# USB_Connector.net
KiCad netlist of a schematic drawn in Altium Designer
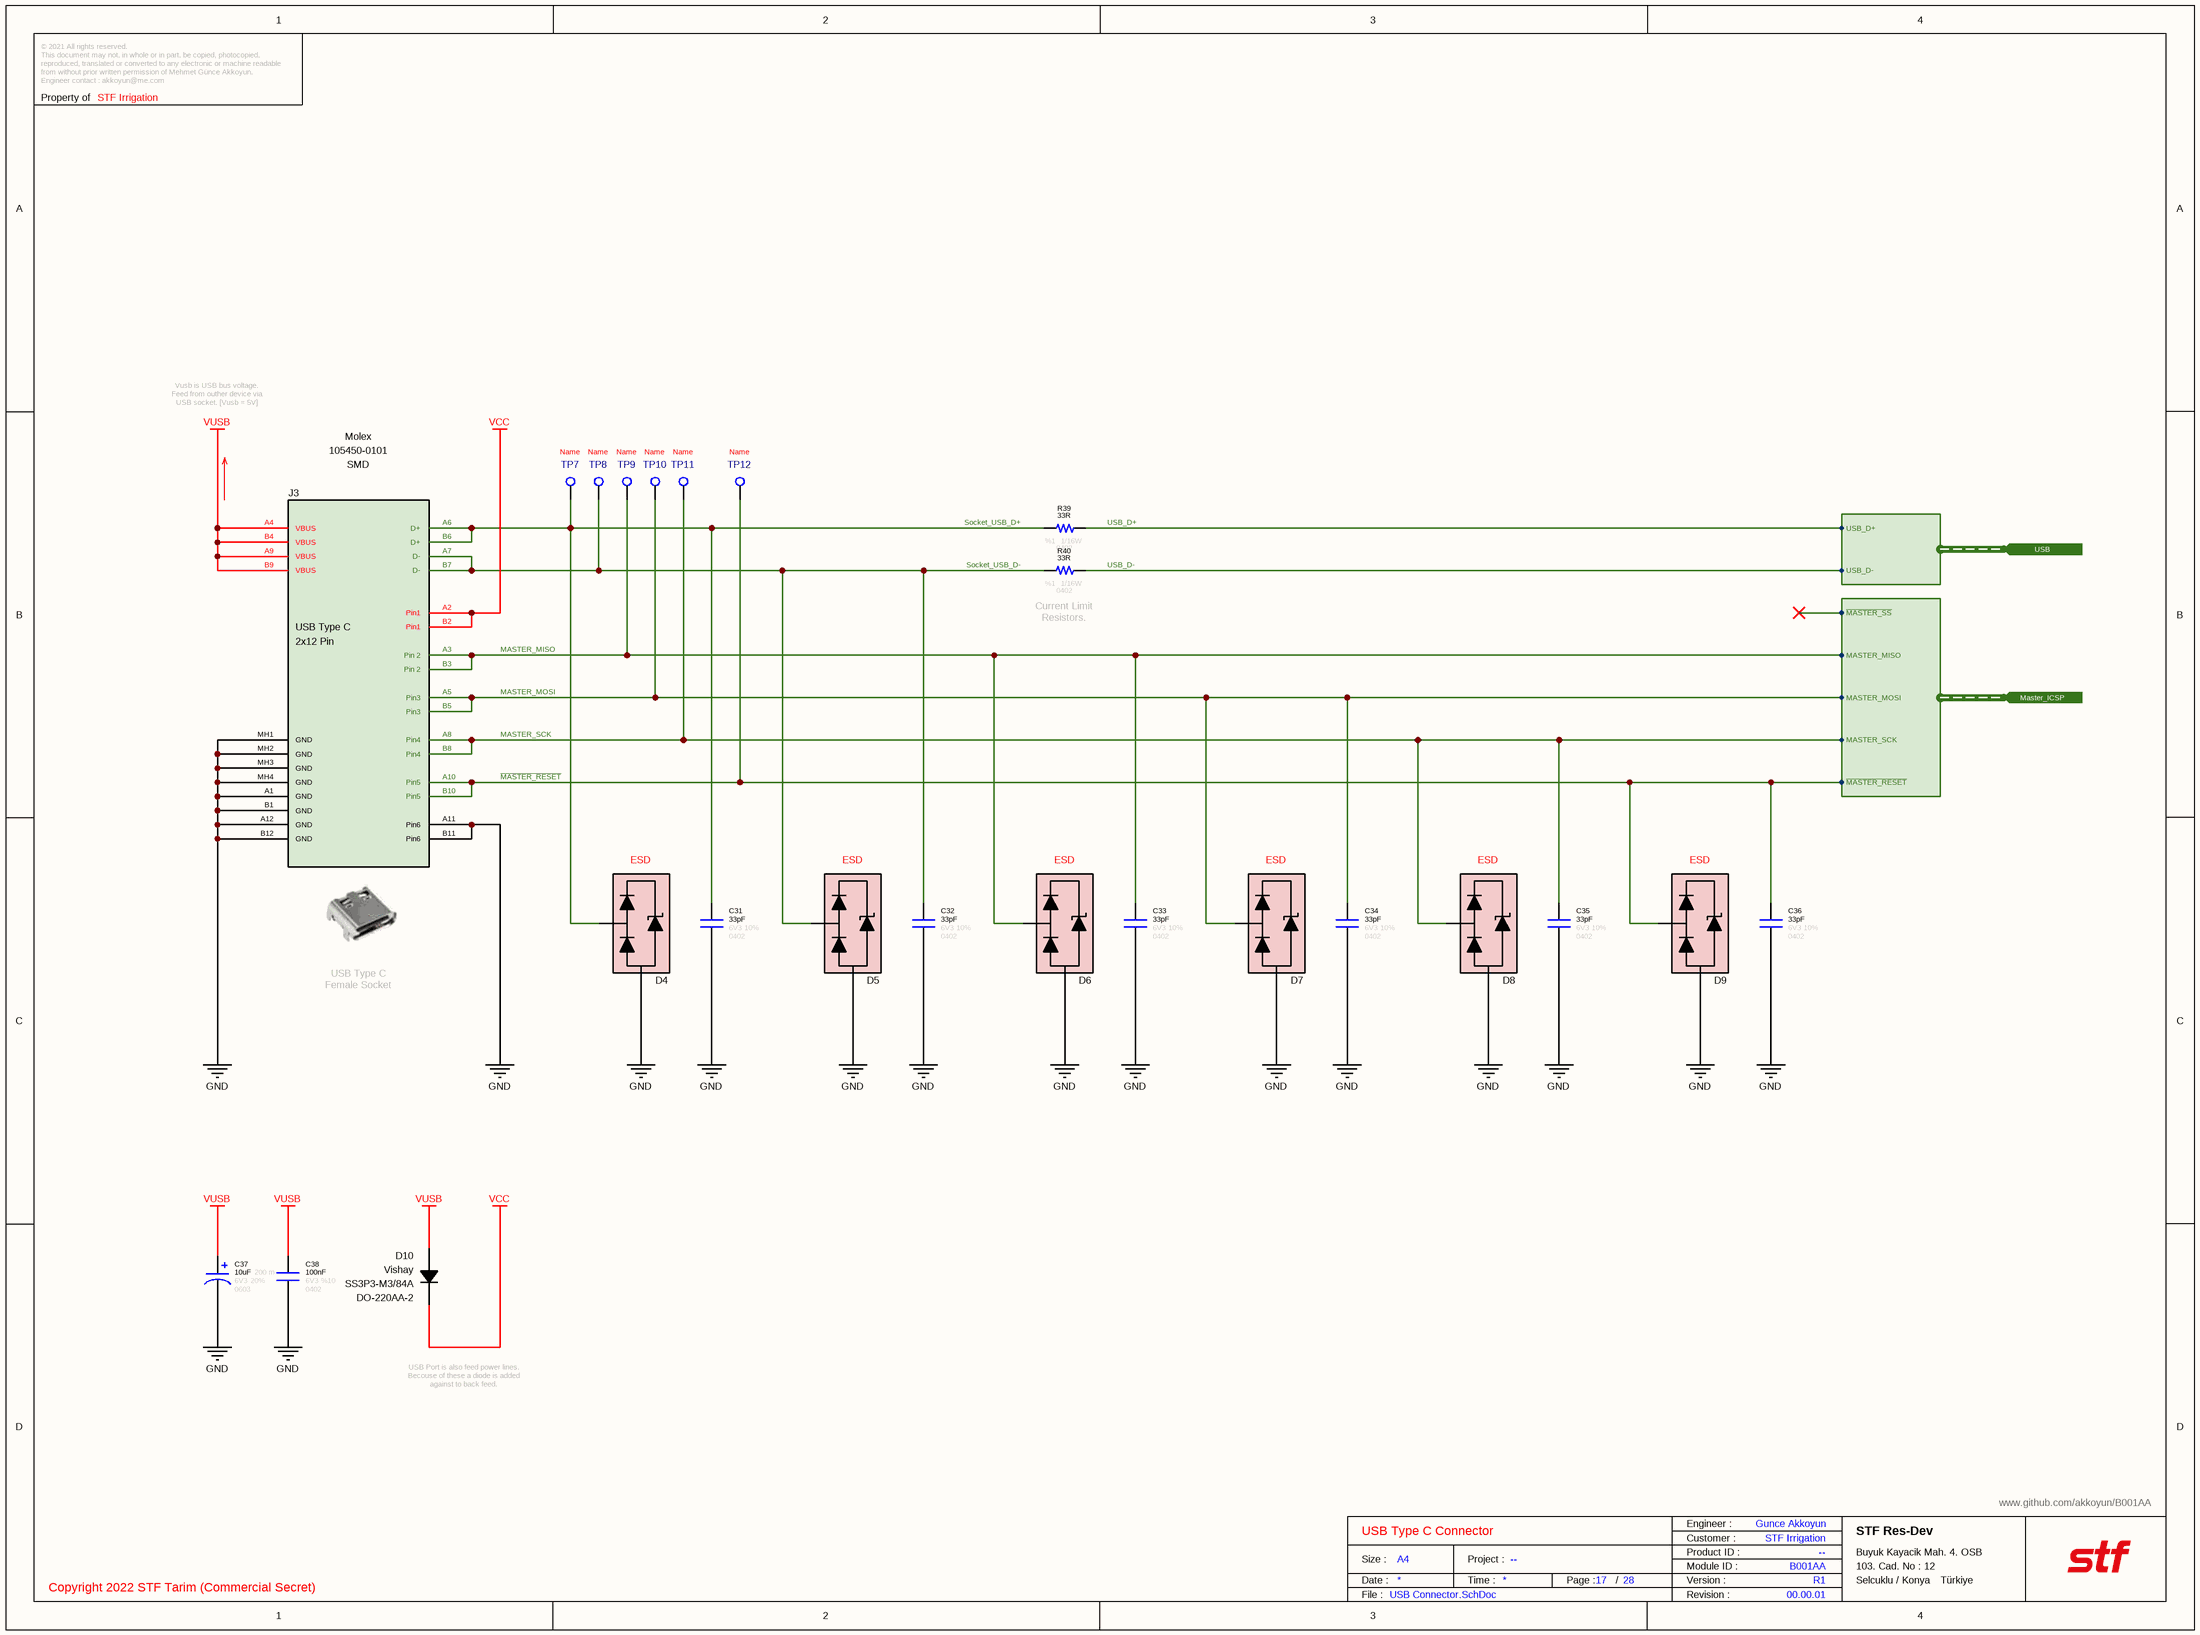
[diagram p0: USB Connector.SchDoc]

(export (version "E")
  (design (tool "Eeschema 10.0.6"))
  (components
    (comp (ref "C31")
      (value "33pF")
      (footprint "CAPACITOR_0402")
      (description "Capacitor - 33pF [0402] (Ceramic)")
      (fields
        (field (name "MANUFACTURER PART NUMBER") "C0402C330J9RACAUTO")
        (field (name "TOLERANCE") "10%")
        (field (name "CASE") "0402")
        (field (name "VOLTAGE") "6V3")
      )
      (libsource (lib "P101DA_Library") (part "Capacitor - 33pF [0402-6V3]"))
    )
    (comp (ref "C32")
      (value "33pF")
      (footprint "CAPACITOR_0402")
      (description "Capacitor - 33pF [0402] (Ceramic)")
      (fields
        (field (name "MANUFACTURER PART NUMBER") "C0402C330J9RACAUTO")
        (field (name "TOLERANCE") "10%")
        (field (name "CASE") "0402")
        (field (name "VOLTAGE") "6V3")
      )
      (libsource (lib "P101DA_Library") (part "Capacitor - 33pF [0402-6V3]"))
    )
    (comp (ref "C33")
      (value "33pF")
      (footprint "CAPACITOR_0402")
      (description "Capacitor - 33pF [0402] (Ceramic)")
      (fields
        (field (name "MANUFACTURER PART NUMBER") "C0402C330J9RACAUTO")
        (field (name "TOLERANCE") "10%")
        (field (name "CASE") "0402")
        (field (name "VOLTAGE") "6V3")
      )
      (libsource (lib "P101DA_Library") (part "Capacitor - 33pF [0402-6V3]"))
    )
    (comp (ref "C34")
      (value "33pF")
      (footprint "CAPACITOR_0402")
      (description "Capacitor - 33pF [0402] (Ceramic)")
      (fields
        (field (name "MANUFACTURER PART NUMBER") "C0402C330J9RACAUTO")
        (field (name "TOLERANCE") "10%")
        (field (name "CASE") "0402")
        (field (name "VOLTAGE") "6V3")
      )
      (libsource (lib "P101DA_Library") (part "Capacitor - 33pF [0402-6V3]"))
    )
    (comp (ref "C35")
      (value "33pF")
      (footprint "CAPACITOR_0402")
      (description "Capacitor - 33pF [0402] (Ceramic)")
      (fields
        (field (name "MANUFACTURER PART NUMBER") "C0402C330J9RACAUTO")
        (field (name "TOLERANCE") "10%")
        (field (name "CASE") "0402")
        (field (name "VOLTAGE") "6V3")
      )
      (libsource (lib "P101DA_Library") (part "Capacitor - 33pF [0402-6V3]"))
    )
    (comp (ref "C36")
      (value "33pF")
      (footprint "CAPACITOR_0402")
      (description "Capacitor - 33pF [0402] (Ceramic)")
      (fields
        (field (name "MANUFACTURER PART NUMBER") "C0402C330J9RACAUTO")
        (field (name "TOLERANCE") "10%")
        (field (name "CASE") "0402")
        (field (name "VOLTAGE") "6V3")
      )
      (libsource (lib "P101DA_Library") (part "Capacitor - 33pF [0402-6V3]"))
    )
    (comp (ref "C37")
      (value "10uF")
      (footprint "CAPACITOR_0603_Tantalum")
      (description "Capacitor - 10uF [0603] (Tantalium)")
      (fields
        (field (name "MANUFACTURER PART NUMBER") "F380J106MMAAH3")
        (field (name "ESR") "200 m")
        (field (name "TOLERANCE") "20%")
        (field (name "CASE") "0603")
        (field (name "VOLTAGE") "6V3")
        (field (name "Comment") "Capacitor - 10uF [0603] (Tantalum)")
      )
      (libsource (lib "P101DA_Library") (part "Capacitor - 10uF [0603-6V3] (Tantalium)"))
    )
    (comp (ref "C38")
      (value "100nF")
      (footprint "CAPACITOR_0402")
      (description "Capacitor - 100nF [0402-6V3] (Ceramic)")
      (fields
        (field (name "MANUFACTURER PART NUMBER") "04026D104KAT4A")
        (field (name "TOLERANCE") "%10")
        (field (name "VOLTAGE") "6V3")
        (field (name "CASE") "0402")
        (field (name "Comment") "Capacitor - 100nF [0402] (Ceramic)")
      )
      (libsource (lib "P101DA_Library") (part "Capacitor - 100nF [0402-6V3]"))
    )
    (comp (ref "D4")
      (value "0402ESDA-MLP1")
      (footprint "ESD_0402")
      (description "SUPPRESSOR ESD 30VDC 0402 HFREE")
      (libsource (lib "P101DA_Library") (part "Diode - TPD1E05U06DPYR"))
    )
    (comp (ref "D5")
      (value "0402ESDA-MLP1")
      (footprint "ESD_0402")
      (description "SUPPRESSOR ESD 30VDC 0402 HFREE")
      (libsource (lib "P101DA_Library") (part "Diode - TPD1E05U06DPYR"))
    )
    (comp (ref "D6")
      (value "0402ESDA-MLP1")
      (footprint "ESD_0402")
      (description "SUPPRESSOR ESD 30VDC 0402 HFREE")
      (libsource (lib "P101DA_Library") (part "Diode - TPD1E05U06DPYR"))
    )
    (comp (ref "D7")
      (value "0402ESDA-MLP1")
      (footprint "ESD_0402")
      (description "SUPPRESSOR ESD 30VDC 0402 HFREE")
      (libsource (lib "P101DA_Library") (part "Diode - TPD1E05U06DPYR"))
    )
    (comp (ref "D8")
      (value "0402ESDA-MLP1")
      (footprint "ESD_0402")
      (description "SUPPRESSOR ESD 30VDC 0402 HFREE")
      (libsource (lib "P101DA_Library") (part "Diode - TPD1E05U06DPYR"))
    )
    (comp (ref "D9")
      (value "0402ESDA-MLP1")
      (footprint "ESD_0402")
      (description "SUPPRESSOR ESD 30VDC 0402 HFREE")
      (libsource (lib "P101DA_Library") (part "Diode - TPD1E05U06DPYR"))
    )
    (comp (ref "D10")
      (value "SS3P3-M3/84A")
      (footprint "DO-220AA-2")
      (description "Schottky Diodes & Rectifiers 3.0 Amp 30 Volt 50 Amp IFSM")
      (fields
        (field (name "MANUFACTURER NAME") "Vishay")
        (field (name "MANUFACTURER PART NUMBER") "SS3P3-M3/84A")
        (field (name "CASE") "DO-220AA-2")
      )
      (libsource (lib "P101DA_Library") (part "Diode - SS3P3M384A"))
    )
    (comp (ref "J3")
      (value "105450-0101")
      (footprint "USB Type C - Molex 105450-0101")
      (description "USB Shielded I/O Receptacle; Type C; Right Angle; Surface Mount; Gold over Nickel")
      (fields
        (field (name "MANUFACTURER NAME") "Molex")
        (field (name "MANUFACTURER PART NUMBER") "105450-0101")
        (field (name "CASE") "SMD")
      )
      (libsource (lib "P101DA_Library") (part "Connector - USB Type C SMD Connector"))
    )
    (comp (ref "R39")
      (value "33R")
      (footprint "RESISTOR_0402")
      (description "Thick Film Resistors - SMD 1/16 W 33 Ohm 1%")
      (fields
        (field (name "MANUFACTURER PART NUMBER") "CRCW040233R0FKED")
        (field (name "CASE") "0402")
        (field (name "TOLERANCE") "%1")
        (field (name "POWER") "1/16W")
        (field (name "Comment") "33R - 0402 - %1 - 1/16W")
      )
      (libsource (lib "P101DA_Library") (part "Resistor - 33R [0402]"))
    )
    (comp (ref "R40")
      (value "33R")
      (footprint "RESISTOR_0402")
      (description "Thick Film Resistors - SMD 1/16 W 33 Ohm 1%")
      (fields
        (field (name "MANUFACTURER PART NUMBER") "CRCW040233R0FKED")
        (field (name "CASE") "0402")
        (field (name "TOLERANCE") "%1")
        (field (name "POWER") "1/16W")
        (field (name "Comment") "33R - 0402 - %1 - 1/16W")
      )
      (libsource (lib "P101DA_Library") (part "Resistor - 33R [0402]"))
    )
    (comp (ref "TP7")
      (value "PCB - Test Point")
      (footprint "Test_Point")
      (description "Test Point")
      (fields (field (name "NAME") "Name"))
      (libsource (lib "P101DA_Library") (part "PCB - Test Point"))
    )
    (comp (ref "TP8")
      (value "PCB - Test Point")
      (footprint "Test_Point")
      (description "Test Point")
      (fields (field (name "NAME") "Name"))
      (libsource (lib "P101DA_Library") (part "PCB - Test Point"))
    )
    (comp (ref "TP9")
      (value "PCB - Test Point")
      (footprint "Test_Point")
      (description "Test Point")
      (fields (field (name "NAME") "Name"))
      (libsource (lib "P101DA_Library") (part "PCB - Test Point"))
    )
    (comp (ref "TP10")
      (value "PCB - Test Point")
      (footprint "Test_Point")
      (description "Test Point")
      (fields (field (name "NAME") "Name"))
      (libsource (lib "P101DA_Library") (part "PCB - Test Point"))
    )
    (comp (ref "TP11")
      (value "PCB - Test Point")
      (footprint "Test_Point")
      (description "Test Point")
      (fields (field (name "NAME") "Name"))
      (libsource (lib "P101DA_Library") (part "PCB - Test Point"))
    )
    (comp (ref "TP12")
      (value "PCB - Test Point")
      (footprint "Test_Point")
      (description "Test Point")
      (fields (field (name "NAME") "Name"))
      (libsource (lib "P101DA_Library") (part "PCB - Test Point"))
    )
  )
  (nets
    (net (code "3") (name "/MASTER_MISO") (class "Default")
      (node (ref "C33") (pin "2") (pinfunction "2_2") (pintype "passive"))
      (node (ref "D6") (pin "1") (pinfunction "I/O_1") (pintype "passive"))
      (node (ref "J3") (pin "A3") (pinfunction "Pin_2_A3") (pintype "passive"))
      (node (ref "J3") (pin "B3") (pinfunction "Pin_2_B3") (pintype "passive"))
      (node (ref "TP9") (pin "1") (pinfunction "1_1") (pintype "passive"))
    )
    (net (code "4") (name "/MASTER_MOSI") (class "Default")
      (node (ref "C34") (pin "2") (pinfunction "2_2") (pintype "passive"))
      (node (ref "D7") (pin "1") (pinfunction "I/O_1") (pintype "passive"))
      (node (ref "J3") (pin "A5") (pinfunction "Pin3_A5") (pintype "passive"))
      (node (ref "J3") (pin "B5") (pinfunction "Pin3_B5") (pintype "passive"))
      (node (ref "TP10") (pin "1") (pinfunction "1_1") (pintype "passive"))
    )
    (net (code "5") (name "/MASTER_SCK") (class "Default")
      (node (ref "C35") (pin "2") (pinfunction "2_2") (pintype "passive"))
      (node (ref "D8") (pin "1") (pinfunction "I/O_1") (pintype "passive"))
      (node (ref "J3") (pin "A8") (pinfunction "Pin4_A8") (pintype "passive"))
      (node (ref "J3") (pin "B8") (pinfunction "Pin4_B8") (pintype "passive"))
      (node (ref "TP11") (pin "1") (pinfunction "1_1") (pintype "passive"))
    )
    (net (code "6") (name "/Socket_USB_D+") (class "Default")
      (node (ref "C31") (pin "2") (pinfunction "2_2") (pintype "passive"))
      (node (ref "D4") (pin "1") (pinfunction "I/O_1") (pintype "passive"))
      (node (ref "J3") (pin "A6") (pinfunction "D+_A6") (pintype "passive"))
      (node (ref "J3") (pin "B6") (pinfunction "D+_B6") (pintype "passive"))
      (node (ref "R39") (pin "2") (pinfunction "2_2") (pintype "passive"))
      (node (ref "TP7") (pin "1") (pinfunction "1_1") (pintype "passive"))
    )
    (net (code "7") (name "/Socket_USB_D-") (class "Default")
      (node (ref "C32") (pin "2") (pinfunction "2_2") (pintype "passive"))
      (node (ref "D5") (pin "1") (pinfunction "I/O_1") (pintype "passive"))
      (node (ref "J3") (pin "A7") (pinfunction "D-_A7") (pintype "passive"))
      (node (ref "J3") (pin "B7") (pinfunction "D-_B7") (pintype "passive"))
      (node (ref "R40") (pin "2") (pinfunction "2_2") (pintype "passive"))
      (node (ref "TP8") (pin "1") (pinfunction "1_1") (pintype "passive"))
    )
    (net (code "8") (name "/USB_D+") (class "Default")
      (node (ref "R39") (pin "1") (pinfunction "1_1") (pintype "passive"))
    )
    (net (code "9") (name "/USB_D-") (class "Default")
      (node (ref "R40") (pin "1") (pinfunction "1_1") (pintype "passive"))
    )
    (net (code "12") (name "/~{MASTER_RESET}") (class "Default")
      (node (ref "C36") (pin "2") (pinfunction "2_2") (pintype "passive"))
      (node (ref "D9") (pin "1") (pinfunction "I/O_1") (pintype "passive"))
      (node (ref "J3") (pin "A10") (pinfunction "Pin5_A10") (pintype "passive"))
      (node (ref "J3") (pin "B10") (pinfunction "Pin5_B10") (pintype "passive"))
      (node (ref "TP12") (pin "1") (pinfunction "1_1") (pintype "passive"))
    )
    (net (code "13") (name "GND") (class "Default")
      (node (ref "C31") (pin "1") (pinfunction "1_1") (pintype "passive"))
      (node (ref "C32") (pin "1") (pinfunction "1_1") (pintype "passive"))
      (node (ref "C33") (pin "1") (pinfunction "1_1") (pintype "passive"))
      (node (ref "C34") (pin "1") (pinfunction "1_1") (pintype "passive"))
      (node (ref "C35") (pin "1") (pinfunction "1_1") (pintype "passive"))
      (node (ref "C36") (pin "1") (pinfunction "1_1") (pintype "passive"))
      (node (ref "C37") (pin "2") (pinfunction "2_2") (pintype "passive"))
      (node (ref "C38") (pin "1") (pinfunction "1_1") (pintype "passive"))
      (node (ref "D4") (pin "2") (pinfunction "GND_2") (pintype "passive"))
      (node (ref "D5") (pin "2") (pinfunction "GND_2") (pintype "passive"))
      (node (ref "D6") (pin "2") (pinfunction "GND_2") (pintype "passive"))
      (node (ref "D7") (pin "2") (pinfunction "GND_2") (pintype "passive"))
      (node (ref "D8") (pin "2") (pinfunction "GND_2") (pintype "passive"))
      (node (ref "D9") (pin "2") (pinfunction "GND_2") (pintype "passive"))
      (node (ref "J3") (pin "A1") (pinfunction "GND_A1") (pintype "passive"))
      (node (ref "J3") (pin "A11") (pinfunction "Pin6_A11") (pintype "passive"))
      (node (ref "J3") (pin "A12") (pinfunction "GND_A12") (pintype "passive"))
      (node (ref "J3") (pin "B1") (pinfunction "GND_B1") (pintype "passive"))
      (node (ref "J3") (pin "B11") (pinfunction "Pin6_B11") (pintype "passive"))
      (node (ref "J3") (pin "B12") (pinfunction "GND_B12") (pintype "passive"))
      (node (ref "J3") (pin "MH1") (pinfunction "GND_MH1") (pintype "passive"))
      (node (ref "J3") (pin "MH2") (pinfunction "GND_MH2") (pintype "passive"))
      (node (ref "J3") (pin "MH3") (pinfunction "GND_MH3") (pintype "passive"))
      (node (ref "J3") (pin "MH4") (pinfunction "GND_MH4") (pintype "passive"))
    )
    (net (code "14") (name "VCC") (class "Default")
      (node (ref "D10") (pin "2") (pinfunction "Cathode_2") (pintype "passive"))
      (node (ref "J3") (pin "A2") (pinfunction "Pin1_A2") (pintype "passive"))
      (node (ref "J3") (pin "B2") (pinfunction "Pin1_B2") (pintype "passive"))
    )
    (net (code "15") (name "VUSB") (class "Default")
      (node (ref "C37") (pin "1") (pinfunction "1_1") (pintype "passive"))
      (node (ref "C38") (pin "2") (pinfunction "2_2") (pintype "passive"))
      (node (ref "D10") (pin "1") (pinfunction "Anode_1") (pintype "passive"))
      (node (ref "J3") (pin "A4") (pinfunction "VBUS_A4") (pintype "passive"))
      (node (ref "J3") (pin "A9") (pinfunction "VBUS_A9") (pintype "passive"))
      (node (ref "J3") (pin "B4") (pinfunction "VBUS_B4") (pintype "passive"))
      (node (ref "J3") (pin "B9") (pinfunction "VBUS_B9") (pintype "passive"))
    )
  )
)
